# Top.net
KiCad netlist of a schematic drawn in Altium Designer
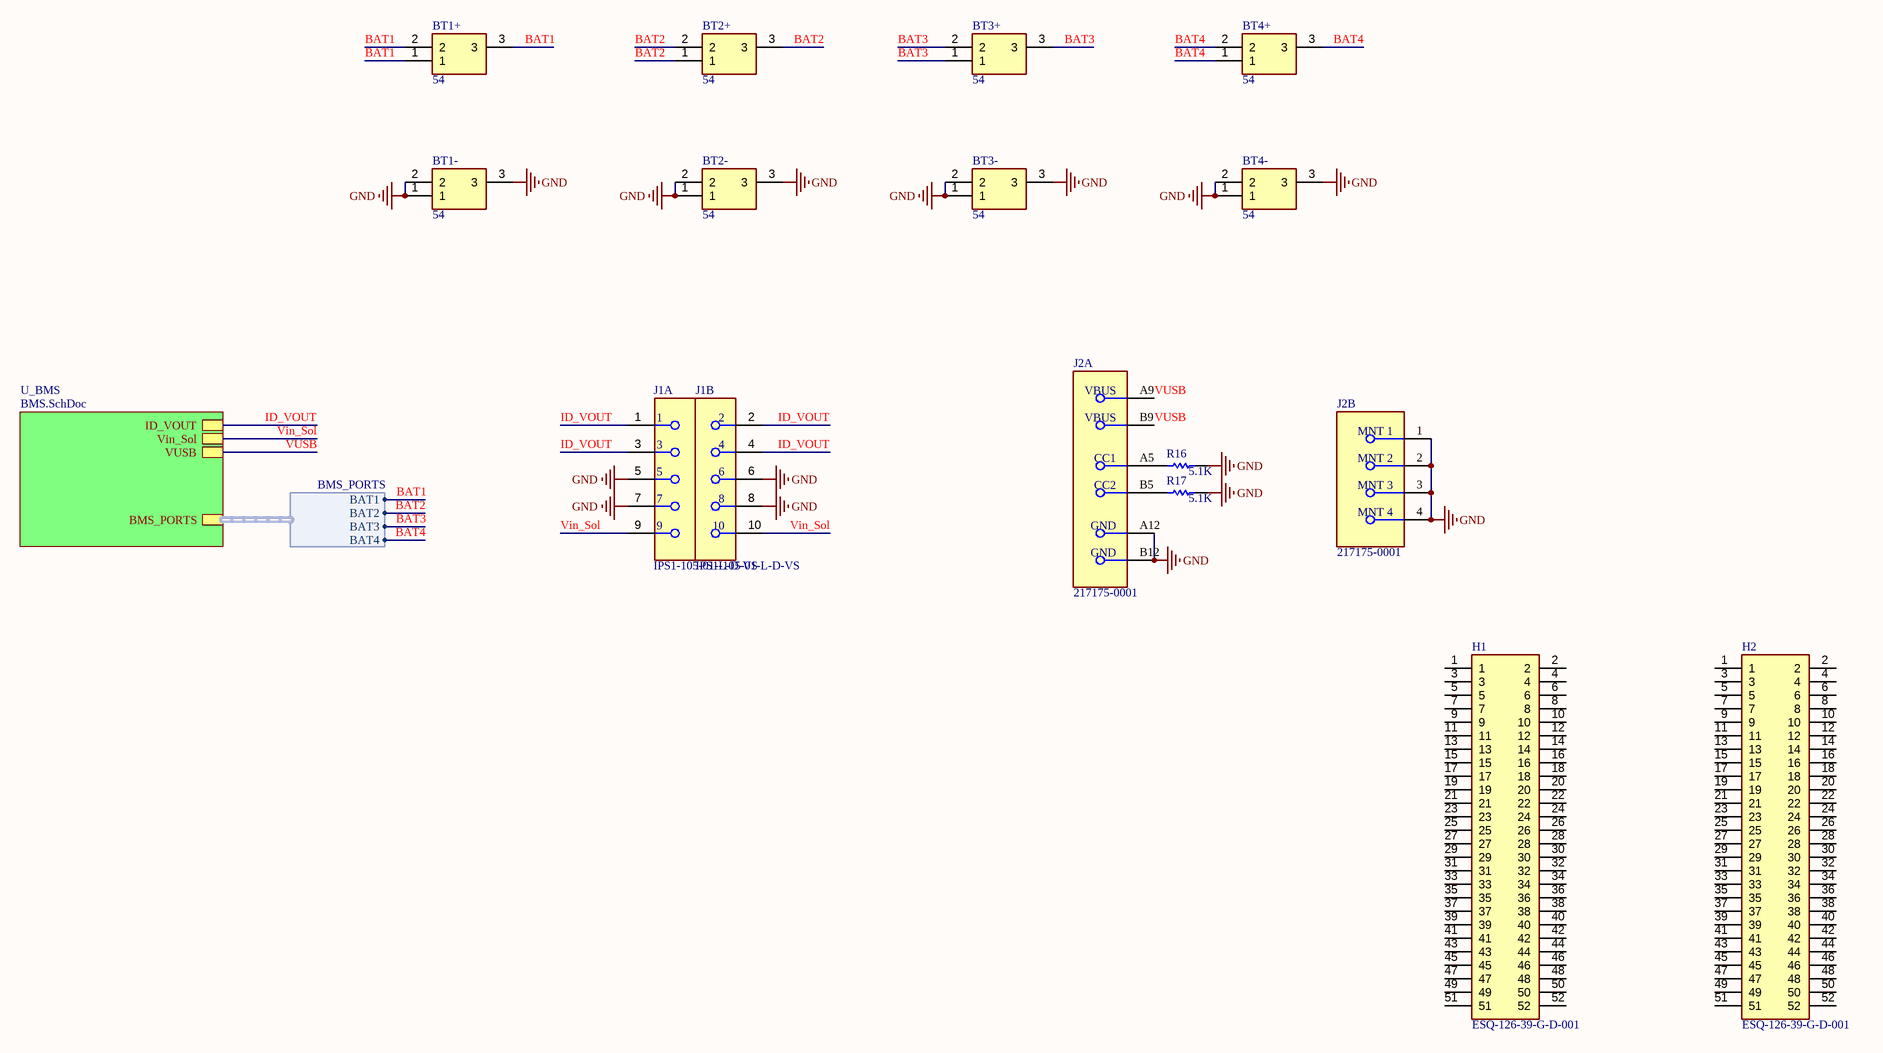
[diagram p0: Top.SchDoc]

(export (version "E")
  (design (tool "Eeschema 10.0.6"))
  (components
    (comp (ref "BT1+")
      (value "54")
      (footprint "54")
      (description "Battery")
      (fields (field (name "MOUSER PART NUMBER") "534-54"))
      (libsource (lib "Hitesh Bhoyar") (part "54"))
    )
    (comp (ref "BT1-")
      (value "54")
      (footprint "54")
      (description "Battery")
      (fields (field (name "MOUSER PART NUMBER") "534-54"))
      (libsource (lib "Hitesh Bhoyar") (part "54"))
    )
    (comp (ref "BT2+")
      (value "54")
      (footprint "54")
      (description "Battery")
      (fields (field (name "MOUSER PART NUMBER") "534-54"))
      (libsource (lib "Hitesh Bhoyar") (part "54"))
    )
    (comp (ref "BT2-")
      (value "54")
      (footprint "54")
      (description "Battery")
      (fields (field (name "MOUSER PART NUMBER") "534-54"))
      (libsource (lib "Hitesh Bhoyar") (part "54"))
    )
    (comp (ref "BT3+")
      (value "54")
      (footprint "54")
      (description "Battery")
      (fields (field (name "MOUSER PART NUMBER") "534-54"))
      (libsource (lib "Hitesh Bhoyar") (part "54"))
    )
    (comp (ref "BT3-")
      (value "54")
      (footprint "54")
      (description "Battery")
      (fields (field (name "MOUSER PART NUMBER") "534-54"))
      (libsource (lib "Hitesh Bhoyar") (part "54"))
    )
    (comp (ref "BT4+")
      (value "54")
      (footprint "54")
      (description "Battery")
      (fields (field (name "MOUSER PART NUMBER") "534-54"))
      (libsource (lib "Hitesh Bhoyar") (part "54"))
    )
    (comp (ref "BT4-")
      (value "54")
      (footprint "54")
      (description "Battery")
      (fields (field (name "MOUSER PART NUMBER") "534-54"))
      (libsource (lib "Hitesh Bhoyar") (part "54"))
    )
    (comp (ref "H1")
      (value "ESQ-126-39-G-D-001")
      (footprint "RHDR52W64P254_2X26_6654X495X1135P")
      (description "PC / 104 Connectors Elevated Socket Strip")
      (fields (field (name "MOUSER PART NUMBER") "200-ESQ12639GD001"))
      (libsource (lib "Hitesh Bhoyar") (part "ESQ-126-39-G-D-001"))
    )
    (comp (ref "H2")
      (value "ESQ-126-39-G-D-001")
      (footprint "RHDR52W64P254_2X26_6654X495X1135P")
      (description "PC / 104 Connectors Elevated Socket Strip")
      (fields (field (name "MOUSER PART NUMBER") "200-ESQ12639GD001"))
      (libsource (lib "Hitesh Bhoyar") (part "ESQ-126-39-G-D-001"))
    )
    (comp (ref "J1")
      (value "IPS1-105-01-L-D-VS")
      (footprint "FP-IPS1-105-01-L-D-VS-MFG")
      (description "CONN RCPT 10POS 0.1 GOLD SMD")
      (fields
        (field (name "MANUFACTURER") "Samtec")
        (field (name "OCTOPART") "https://octopart.com/ips1-105-01-l-d-vs-samtec-19544880")
      )
      (libsource (lib "") (part "393b6539e713c610e9ddbd64c51154e_1"))
    )
    (comp (ref "J2")
      (value "217175-0001")
      (footprint "FP-217175-0001-MFG")
      (description "CONN RCP USB2.0 C 6+18P SMD RA")
      (libsource (lib "Altium Content Vault") (part "6a66c69350f09309f94811689c98437"))
    )
    (comp (ref "R16")
      (value "5.1K")
      (footprint "RESC1608X55X30LL15T15")
      (fields (field (name "PART NUMBER") "ERJ-3GEYJ512V") (field (name "MANUFACTURER") "Panasonic"))
      (libsource (lib "Altium Content Vault") (part "RES"))
    )
    (comp (ref "R17")
      (value "5.1K")
      (footprint "RESC1608X55X30LL15T15")
      (fields (field (name "PART NUMBER") "ERJ-3GEYJ512V") (field (name "MANUFACTURER") "Panasonic"))
      (libsource (lib "Altium Content Vault") (part "RES"))
    )
  )
  (nets
    (net (code "2") (name "/BAT1") (class "Default")
      (node (ref "BT1+") (pin "1") (pinfunction "1_1") (pintype "passive"))
      (node (ref "BT1+") (pin "2") (pinfunction "2_2") (pintype "passive"))
      (node (ref "BT1+") (pin "3") (pinfunction "3_3") (pintype "passive"))
    )
    (net (code "3") (name "/BAT2") (class "Default")
      (node (ref "BT2+") (pin "1") (pinfunction "1_1") (pintype "passive"))
      (node (ref "BT2+") (pin "2") (pinfunction "2_2") (pintype "passive"))
      (node (ref "BT2+") (pin "3") (pinfunction "3_3") (pintype "passive"))
    )
    (net (code "4") (name "/BAT3") (class "Default")
      (node (ref "BT3+") (pin "1") (pinfunction "1_1") (pintype "passive"))
      (node (ref "BT3+") (pin "2") (pinfunction "2_2") (pintype "passive"))
      (node (ref "BT3+") (pin "3") (pinfunction "3_3") (pintype "passive"))
    )
    (net (code "5") (name "/BAT4") (class "Default")
      (node (ref "BT4+") (pin "1") (pinfunction "1_1") (pintype "passive"))
      (node (ref "BT4+") (pin "2") (pinfunction "2_2") (pintype "passive"))
      (node (ref "BT4+") (pin "3") (pinfunction "3_3") (pintype "passive"))
    )
    (net (code "6") (name "/ID_VOUT") (class "Default")
      (node (ref "J1") (pin "1") (pinfunction "1_1") (pintype "passive"))
      (node (ref "J1") (pin "2") (pinfunction "2_2") (pintype "passive"))
      (node (ref "J1") (pin "3") (pinfunction "3_3") (pintype "passive"))
      (node (ref "J1") (pin "4") (pinfunction "4_4") (pintype "passive"))
    )
    (net (code "7") (name "/VUSB") (class "Default")
      (node (ref "J2") (pin "A9") (pinfunction "VBUS_A9") (pintype "power_in"))
      (node (ref "J2") (pin "B9") (pinfunction "VBUS_B9") (pintype "power_in"))
    )
    (net (code "8") (name "/Vin_Sol") (class "Default")
      (node (ref "J1") (pin "10") (pinfunction "10_10") (pintype "passive"))
      (node (ref "J1") (pin "9") (pinfunction "9_9") (pintype "passive"))
    )
    (net (code "10") (name "GND") (class "Default")
      (node (ref "BT1-") (pin "1") (pinfunction "1_1") (pintype "passive"))
      (node (ref "BT1-") (pin "2") (pinfunction "2_2") (pintype "passive"))
      (node (ref "BT1-") (pin "3") (pinfunction "3_3") (pintype "passive"))
      (node (ref "BT2-") (pin "1") (pinfunction "1_1") (pintype "passive"))
      (node (ref "BT2-") (pin "2") (pinfunction "2_2") (pintype "passive"))
      (node (ref "BT2-") (pin "3") (pinfunction "3_3") (pintype "passive"))
      (node (ref "BT3-") (pin "1") (pinfunction "1_1") (pintype "passive"))
      (node (ref "BT3-") (pin "2") (pinfunction "2_2") (pintype "passive"))
      (node (ref "BT3-") (pin "3") (pinfunction "3_3") (pintype "passive"))
      (node (ref "BT4-") (pin "1") (pinfunction "1_1") (pintype "passive"))
      (node (ref "BT4-") (pin "2") (pinfunction "2_2") (pintype "passive"))
      (node (ref "BT4-") (pin "3") (pinfunction "3_3") (pintype "passive"))
      (node (ref "J1") (pin "5") (pinfunction "5_5") (pintype "passive"))
      (node (ref "J1") (pin "6") (pinfunction "6_6") (pintype "passive"))
      (node (ref "J1") (pin "7") (pinfunction "7_7") (pintype "passive"))
      (node (ref "J1") (pin "8") (pinfunction "8_8") (pintype "passive"))
      (node (ref "J2") (pin "1") (pinfunction "MNT_1_1") (pintype "passive"))
      (node (ref "J2") (pin "2") (pinfunction "MNT_2_2") (pintype "passive"))
      (node (ref "J2") (pin "3") (pinfunction "MNT_3_3") (pintype "passive"))
      (node (ref "J2") (pin "4") (pinfunction "MNT_4_4") (pintype "passive"))
      (node (ref "J2") (pin "A12") (pinfunction "GND_A12") (pintype "power_in"))
      (node (ref "J2") (pin "B12") (pinfunction "GND_B12") (pintype "power_in"))
      (node (ref "R16") (pin "2") (pinfunction "2_2") (pintype "passive"))
      (node (ref "R17") (pin "2") (pinfunction "2_2") (pintype "passive"))
    )
    (net (code "11") (name "Net-(J2A-CC1)") (class "Default")
      (node (ref "J2") (pin "A5") (pinfunction "CC1_A5") (pintype "passive"))
      (node (ref "R16") (pin "1") (pinfunction "1_1") (pintype "passive"))
    )
    (net (code "12") (name "Net-(J2A-CC2)") (class "Default")
      (node (ref "J2") (pin "B5") (pinfunction "CC2_B5") (pintype "passive"))
      (node (ref "R17") (pin "1") (pinfunction "1_1") (pintype "passive"))
    )
    (net (code "13") (name "unconnected-(H1-Pad1)") (class "Default")
      (node (ref "H1") (pin "1") (pinfunction "1_1") (pintype "passive"))
    )
    (net (code "14") (name "unconnected-(H1-Pad2)") (class "Default")
      (node (ref "H1") (pin "2") (pinfunction "2_2") (pintype "passive"))
    )
    (net (code "15") (name "unconnected-(H1-Pad3)") (class "Default")
      (node (ref "H1") (pin "3") (pinfunction "3_3") (pintype "passive"))
    )
    (net (code "16") (name "unconnected-(H1-Pad4)") (class "Default")
      (node (ref "H1") (pin "4") (pinfunction "4_4") (pintype "passive"))
    )
    (net (code "17") (name "unconnected-(H1-Pad5)") (class "Default")
      (node (ref "H1") (pin "5") (pinfunction "5_5") (pintype "passive"))
    )
    (net (code "18") (name "unconnected-(H1-Pad6)") (class "Default")
      (node (ref "H1") (pin "6") (pinfunction "6_6") (pintype "passive"))
    )
    (net (code "19") (name "unconnected-(H1-Pad7)") (class "Default")
      (node (ref "H1") (pin "7") (pinfunction "7_7") (pintype "passive"))
    )
    (net (code "20") (name "unconnected-(H1-Pad8)") (class "Default")
      (node (ref "H1") (pin "8") (pinfunction "8_8") (pintype "passive"))
    )
    (net (code "21") (name "unconnected-(H1-Pad9)") (class "Default")
      (node (ref "H1") (pin "9") (pinfunction "9_9") (pintype "passive"))
    )
    (net (code "22") (name "unconnected-(H1-Pad10)") (class "Default")
      (node (ref "H1") (pin "10") (pinfunction "10_10") (pintype "passive"))
    )
    (net (code "23") (name "unconnected-(H1-Pad11)") (class "Default")
      (node (ref "H1") (pin "11") (pinfunction "11_11") (pintype "passive"))
    )
    (net (code "24") (name "unconnected-(H1-Pad12)") (class "Default")
      (node (ref "H1") (pin "12") (pinfunction "12_12") (pintype "passive"))
    )
    (net (code "25") (name "unconnected-(H1-Pad13)") (class "Default")
      (node (ref "H1") (pin "13") (pinfunction "13_13") (pintype "passive"))
    )
    (net (code "26") (name "unconnected-(H1-Pad14)") (class "Default")
      (node (ref "H1") (pin "14") (pinfunction "14_14") (pintype "passive"))
    )
    (net (code "27") (name "unconnected-(H1-Pad15)") (class "Default")
      (node (ref "H1") (pin "15") (pinfunction "15_15") (pintype "passive"))
    )
    (net (code "28") (name "unconnected-(H1-Pad16)") (class "Default")
      (node (ref "H1") (pin "16") (pinfunction "16_16") (pintype "passive"))
    )
    (net (code "29") (name "unconnected-(H1-Pad17)") (class "Default")
      (node (ref "H1") (pin "17") (pinfunction "17_17") (pintype "passive"))
    )
    (net (code "30") (name "unconnected-(H1-Pad18)") (class "Default")
      (node (ref "H1") (pin "18") (pinfunction "18_18") (pintype "passive"))
    )
    (net (code "31") (name "unconnected-(H1-Pad19)") (class "Default")
      (node (ref "H1") (pin "19") (pinfunction "19_19") (pintype "passive"))
    )
    (net (code "32") (name "unconnected-(H1-Pad20)") (class "Default")
      (node (ref "H1") (pin "20") (pinfunction "20_20") (pintype "passive"))
    )
    (net (code "33") (name "unconnected-(H1-Pad21)") (class "Default")
      (node (ref "H1") (pin "21") (pinfunction "21_21") (pintype "passive"))
    )
    (net (code "34") (name "unconnected-(H1-Pad22)") (class "Default")
      (node (ref "H1") (pin "22") (pinfunction "22_22") (pintype "passive"))
    )
    (net (code "35") (name "unconnected-(H1-Pad23)") (class "Default")
      (node (ref "H1") (pin "23") (pinfunction "23_23") (pintype "passive"))
    )
    (net (code "36") (name "unconnected-(H1-Pad24)") (class "Default")
      (node (ref "H1") (pin "24") (pinfunction "24_24") (pintype "passive"))
    )
    (net (code "37") (name "unconnected-(H1-Pad25)") (class "Default")
      (node (ref "H1") (pin "25") (pinfunction "25_25") (pintype "passive"))
    )
    (net (code "38") (name "unconnected-(H1-Pad26)") (class "Default")
      (node (ref "H1") (pin "26") (pinfunction "26_26") (pintype "passive"))
    )
    (net (code "39") (name "unconnected-(H1-Pad27)") (class "Default")
      (node (ref "H1") (pin "27") (pinfunction "27_27") (pintype "passive"))
    )
    (net (code "40") (name "unconnected-(H1-Pad28)") (class "Default")
      (node (ref "H1") (pin "28") (pinfunction "28_28") (pintype "passive"))
    )
    (net (code "41") (name "unconnected-(H1-Pad29)") (class "Default")
      (node (ref "H1") (pin "29") (pinfunction "29_29") (pintype "passive"))
    )
    (net (code "42") (name "unconnected-(H1-Pad30)") (class "Default")
      (node (ref "H1") (pin "30") (pinfunction "30_30") (pintype "passive"))
    )
    (net (code "43") (name "unconnected-(H1-Pad31)") (class "Default")
      (node (ref "H1") (pin "31") (pinfunction "31_31") (pintype "passive"))
    )
    (net (code "44") (name "unconnected-(H1-Pad32)") (class "Default")
      (node (ref "H1") (pin "32") (pinfunction "32_32") (pintype "passive"))
    )
    (net (code "45") (name "unconnected-(H1-Pad33)") (class "Default")
      (node (ref "H1") (pin "33") (pinfunction "33_33") (pintype "passive"))
    )
    (net (code "46") (name "unconnected-(H1-Pad34)") (class "Default")
      (node (ref "H1") (pin "34") (pinfunction "34_34") (pintype "passive"))
    )
    (net (code "47") (name "unconnected-(H1-Pad35)") (class "Default")
      (node (ref "H1") (pin "35") (pinfunction "35_35") (pintype "passive"))
    )
    (net (code "48") (name "unconnected-(H1-Pad36)") (class "Default")
      (node (ref "H1") (pin "36") (pinfunction "36_36") (pintype "passive"))
    )
    (net (code "49") (name "unconnected-(H1-Pad37)") (class "Default")
      (node (ref "H1") (pin "37") (pinfunction "37_37") (pintype "passive"))
    )
    (net (code "50") (name "unconnected-(H1-Pad38)") (class "Default")
      (node (ref "H1") (pin "38") (pinfunction "38_38") (pintype "passive"))
    )
    (net (code "51") (name "unconnected-(H1-Pad39)") (class "Default")
      (node (ref "H1") (pin "39") (pinfunction "39_39") (pintype "passive"))
    )
    (net (code "52") (name "unconnected-(H1-Pad40)") (class "Default")
      (node (ref "H1") (pin "40") (pinfunction "40_40") (pintype "passive"))
    )
    (net (code "53") (name "unconnected-(H1-Pad41)") (class "Default")
      (node (ref "H1") (pin "41") (pinfunction "41_41") (pintype "passive"))
    )
    (net (code "54") (name "unconnected-(H1-Pad42)") (class "Default")
      (node (ref "H1") (pin "42") (pinfunction "42_42") (pintype "passive"))
    )
    (net (code "55") (name "unconnected-(H1-Pad43)") (class "Default")
      (node (ref "H1") (pin "43") (pinfunction "43_43") (pintype "passive"))
    )
    (net (code "56") (name "unconnected-(H1-Pad44)") (class "Default")
      (node (ref "H1") (pin "44") (pinfunction "44_44") (pintype "passive"))
    )
    (net (code "57") (name "unconnected-(H1-Pad45)") (class "Default")
      (node (ref "H1") (pin "45") (pinfunction "45_45") (pintype "passive"))
    )
    (net (code "58") (name "unconnected-(H1-Pad46)") (class "Default")
      (node (ref "H1") (pin "46") (pinfunction "46_46") (pintype "passive"))
    )
    (net (code "59") (name "unconnected-(H1-Pad47)") (class "Default")
      (node (ref "H1") (pin "47") (pinfunction "47_47") (pintype "passive"))
    )
    (net (code "60") (name "unconnected-(H1-Pad48)") (class "Default")
      (node (ref "H1") (pin "48") (pinfunction "48_48") (pintype "passive"))
    )
    (net (code "61") (name "unconnected-(H1-Pad49)") (class "Default")
      (node (ref "H1") (pin "49") (pinfunction "49_49") (pintype "passive"))
    )
    (net (code "62") (name "unconnected-(H1-Pad50)") (class "Default")
      (node (ref "H1") (pin "50") (pinfunction "50_50") (pintype "passive"))
    )
    (net (code "63") (name "unconnected-(H1-Pad51)") (class "Default")
      (node (ref "H1") (pin "51") (pinfunction "51_51") (pintype "passive"))
    )
    (net (code "64") (name "unconnected-(H1-Pad52)") (class "Default")
      (node (ref "H1") (pin "52") (pinfunction "52_52") (pintype "passive"))
    )
    (net (code "65") (name "unconnected-(H2-Pad1)") (class "Default")
      (node (ref "H2") (pin "1") (pinfunction "1_1") (pintype "passive"))
    )
    (net (code "66") (name "unconnected-(H2-Pad2)") (class "Default")
      (node (ref "H2") (pin "2") (pinfunction "2_2") (pintype "passive"))
    )
    (net (code "67") (name "unconnected-(H2-Pad3)") (class "Default")
      (node (ref "H2") (pin "3") (pinfunction "3_3") (pintype "passive"))
    )
    (net (code "68") (name "unconnected-(H2-Pad4)") (class "Default")
      (node (ref "H2") (pin "4") (pinfunction "4_4") (pintype "passive"))
    )
    (net (code "69") (name "unconnected-(H2-Pad5)") (class "Default")
      (node (ref "H2") (pin "5") (pinfunction "5_5") (pintype "passive"))
    )
    (net (code "70") (name "unconnected-(H2-Pad6)") (class "Default")
      (node (ref "H2") (pin "6") (pinfunction "6_6") (pintype "passive"))
    )
    (net (code "71") (name "unconnected-(H2-Pad7)") (class "Default")
      (node (ref "H2") (pin "7") (pinfunction "7_7") (pintype "passive"))
    )
    (net (code "72") (name "unconnected-(H2-Pad8)") (class "Default")
      (node (ref "H2") (pin "8") (pinfunction "8_8") (pintype "passive"))
    )
    (net (code "73") (name "unconnected-(H2-Pad9)") (class "Default")
      (node (ref "H2") (pin "9") (pinfunction "9_9") (pintype "passive"))
    )
    (net (code "74") (name "unconnected-(H2-Pad10)") (class "Default")
      (node (ref "H2") (pin "10") (pinfunction "10_10") (pintype "passive"))
    )
    (net (code "75") (name "unconnected-(H2-Pad11)") (class "Default")
      (node (ref "H2") (pin "11") (pinfunction "11_11") (pintype "passive"))
    )
    (net (code "76") (name "unconnected-(H2-Pad12)") (class "Default")
      (node (ref "H2") (pin "12") (pinfunction "12_12") (pintype "passive"))
    )
    (net (code "77") (name "unconnected-(H2-Pad13)") (class "Default")
      (node (ref "H2") (pin "13") (pinfunction "13_13") (pintype "passive"))
    )
    (net (code "78") (name "unconnected-(H2-Pad14)") (class "Default")
      (node (ref "H2") (pin "14") (pinfunction "14_14") (pintype "passive"))
    )
    (net (code "79") (name "unconnected-(H2-Pad15)") (class "Default")
      (node (ref "H2") (pin "15") (pinfunction "15_15") (pintype "passive"))
    )
    (net (code "80") (name "unconnected-(H2-Pad16)") (class "Default")
      (node (ref "H2") (pin "16") (pinfunction "16_16") (pintype "passive"))
    )
    (net (code "81") (name "unconnected-(H2-Pad17)") (class "Default")
      (node (ref "H2") (pin "17") (pinfunction "17_17") (pintype "passive"))
    )
    (net (code "82") (name "unconnected-(H2-Pad18)") (class "Default")
      (node (ref "H2") (pin "18") (pinfunction "18_18") (pintype "passive"))
    )
    (net (code "83") (name "unconnected-(H2-Pad19)") (class "Default")
      (node (ref "H2") (pin "19") (pinfunction "19_19") (pintype "passive"))
    )
    (net (code "84") (name "unconnected-(H2-Pad20)") (class "Default")
      (node (ref "H2") (pin "20") (pinfunction "20_20") (pintype "passive"))
    )
    (net (code "85") (name "unconnected-(H2-Pad21)") (class "Default")
      (node (ref "H2") (pin "21") (pinfunction "21_21") (pintype "passive"))
    )
    (net (code "86") (name "unconnected-(H2-Pad22)") (class "Default")
      (node (ref "H2") (pin "22") (pinfunction "22_22") (pintype "passive"))
    )
    (net (code "87") (name "unconnected-(H2-Pad23)") (class "Default")
      (node (ref "H2") (pin "23") (pinfunction "23_23") (pintype "passive"))
    )
    (net (code "88") (name "unconnected-(H2-Pad24)") (class "Default")
      (node (ref "H2") (pin "24") (pinfunction "24_24") (pintype "passive"))
    )
    (net (code "89") (name "unconnected-(H2-Pad25)") (class "Default")
      (node (ref "H2") (pin "25") (pinfunction "25_25") (pintype "passive"))
    )
    (net (code "90") (name "unconnected-(H2-Pad26)") (class "Default")
      (node (ref "H2") (pin "26") (pinfunction "26_26") (pintype "passive"))
    )
    (net (code "91") (name "unconnected-(H2-Pad27)") (class "Default")
      (node (ref "H2") (pin "27") (pinfunction "27_27") (pintype "passive"))
    )
    (net (code "92") (name "unconnected-(H2-Pad28)") (class "Default")
      (node (ref "H2") (pin "28") (pinfunction "28_28") (pintype "passive"))
    )
    (net (code "93") (name "unconnected-(H2-Pad29)") (class "Default")
      (node (ref "H2") (pin "29") (pinfunction "29_29") (pintype "passive"))
    )
    (net (code "94") (name "unconnected-(H2-Pad30)") (class "Default")
      (node (ref "H2") (pin "30") (pinfunction "30_30") (pintype "passive"))
    )
    (net (code "95") (name "unconnected-(H2-Pad31)") (class "Default")
      (node (ref "H2") (pin "31") (pinfunction "31_31") (pintype "passive"))
    )
    (net (code "96") (name "unconnected-(H2-Pad32)") (class "Default")
      (node (ref "H2") (pin "32") (pinfunction "32_32") (pintype "passive"))
    )
    (net (code "97") (name "unconnected-(H2-Pad33)") (class "Default")
      (node (ref "H2") (pin "33") (pinfunction "33_33") (pintype "passive"))
    )
    (net (code "98") (name "unconnected-(H2-Pad34)") (class "Default")
      (node (ref "H2") (pin "34") (pinfunction "34_34") (pintype "passive"))
    )
    (net (code "99") (name "unconnected-(H2-Pad35)") (class "Default")
      (node (ref "H2") (pin "35") (pinfunction "35_35") (pintype "passive"))
    )
    (net (code "100") (name "unconnected-(H2-Pad36)") (class "Default")
      (node (ref "H2") (pin "36") (pinfunction "36_36") (pintype "passive"))
    )
    (net (code "101") (name "unconnected-(H2-Pad37)") (class "Default")
      (node (ref "H2") (pin "37") (pinfunction "37_37") (pintype "passive"))
    )
    (net (code "102") (name "unconnected-(H2-Pad38)") (class "Default")
      (node (ref "H2") (pin "38") (pinfunction "38_38") (pintype "passive"))
    )
    (net (code "103") (name "unconnected-(H2-Pad39)") (class "Default")
      (node (ref "H2") (pin "39") (pinfunction "39_39") (pintype "passive"))
    )
    (net (code "104") (name "unconnected-(H2-Pad40)") (class "Default")
      (node (ref "H2") (pin "40") (pinfunction "40_40") (pintype "passive"))
    )
    (net (code "105") (name "unconnected-(H2-Pad41)") (class "Default")
      (node (ref "H2") (pin "41") (pinfunction "41_41") (pintype "passive"))
    )
    (net (code "106") (name "unconnected-(H2-Pad42)") (class "Default")
      (node (ref "H2") (pin "42") (pinfunction "42_42") (pintype "passive"))
    )
    (net (code "107") (name "unconnected-(H2-Pad43)") (class "Default")
      (node (ref "H2") (pin "43") (pinfunction "43_43") (pintype "passive"))
    )
    (net (code "108") (name "unconnected-(H2-Pad44)") (class "Default")
      (node (ref "H2") (pin "44") (pinfunction "44_44") (pintype "passive"))
    )
    (net (code "109") (name "unconnected-(H2-Pad45)") (class "Default")
      (node (ref "H2") (pin "45") (pinfunction "45_45") (pintype "passive"))
    )
    (net (code "110") (name "unconnected-(H2-Pad46)") (class "Default")
      (node (ref "H2") (pin "46") (pinfunction "46_46") (pintype "passive"))
    )
    (net (code "111") (name "unconnected-(H2-Pad47)") (class "Default")
      (node (ref "H2") (pin "47") (pinfunction "47_47") (pintype "passive"))
    )
    (net (code "112") (name "unconnected-(H2-Pad48)") (class "Default")
      (node (ref "H2") (pin "48") (pinfunction "48_48") (pintype "passive"))
    )
    (net (code "113") (name "unconnected-(H2-Pad49)") (class "Default")
      (node (ref "H2") (pin "49") (pinfunction "49_49") (pintype "passive"))
    )
    (net (code "114") (name "unconnected-(H2-Pad50)") (class "Default")
      (node (ref "H2") (pin "50") (pinfunction "50_50") (pintype "passive"))
    )
    (net (code "115") (name "unconnected-(H2-Pad51)") (class "Default")
      (node (ref "H2") (pin "51") (pinfunction "51_51") (pintype "passive"))
    )
    (net (code "116") (name "unconnected-(H2-Pad52)") (class "Default")
      (node (ref "H2") (pin "52") (pinfunction "52_52") (pintype "passive"))
    )
  )
)
